# GR_Alim.net
KiCad netlist of a schematic drawn in Altium Designer
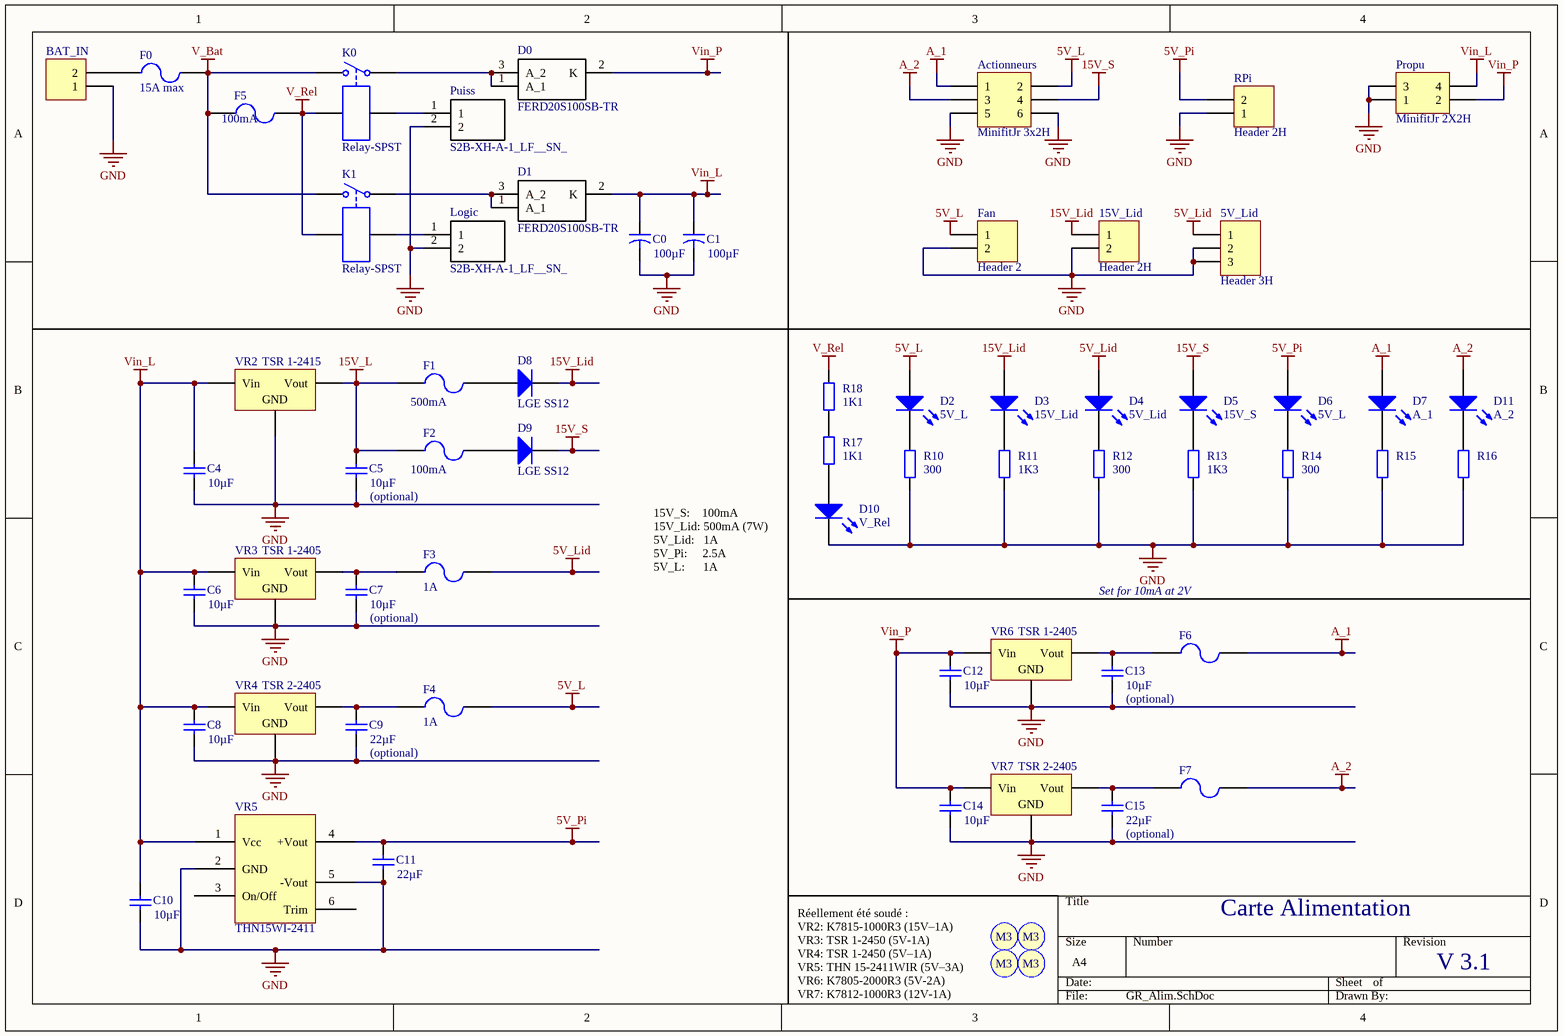
[diagram p0: GR_Alim.SchDoc]

(export (version "E")
  (design (tool "Eeschema 10.0.6"))
  (components
    (comp (ref "5V_Lid")
      (value "Header 3H")
      (footprint "S3B-XH-A")
      (description "Header, 3-Pin, Right Angle")
      (fields (field (name "PUBLISHER") "Altium Limited"))
      (libsource (lib "Miscellaneous Connectors") (part "Header 3H"))
    )
    (comp (ref "15V_Lid")
      (value "Header 2H")
      (footprint "S2B-XH-A")
      (description "Header, 2-Pin, Right Angle")
      (fields (field (name "PUBLISHER") "Altium Limited"))
      (libsource (lib "Miscellaneous Connectors") (part "Header 2H"))
    )
    (comp (ref "Actionneurs")
      (value "MinifitJr 3x2H")
      (footprint "MOLEX_MINIFITJR_3X2H")
      (description "Header, 3-Pin, Dual row, Right Angle")
      (fields (field (name "PUBLISHER") "Altium Limited"))
      (libsource (lib "Miscellaneous Connectors") (part "Header 3X2H"))
    )
    (comp (ref "BAT_IN")
      (value "Battery Onboard Solder")
      (footprint "Battery SALE")
      (description "Header, 2-Pin")
      (fields (field (name "PUBLISHER") "Altium Limited"))
      (libsource (lib "Miscellaneous Connectors") (part "Header 2"))
    )
    (comp (ref "C0")
      (value "100µF")
      (footprint "Condensateur")
      (description "Capacitor")
      (fields (field (name "Comment") "Cap2") (field (name "PUBLISHER") "Altium Limited"))
      (libsource (lib "Miscellaneous Devices") (part "Cap2"))
    )
    (comp (ref "C1")
      (value "100µF")
      (footprint "Condensateur")
      (description "Capacitor")
      (fields (field (name "Comment") "Cap2") (field (name "PUBLISHER") "Altium Limited"))
      (libsource (lib "Miscellaneous Devices") (part "Cap2"))
    )
    (comp (ref "C4")
      (value "10µF")
      (footprint "Capacitor 1206")
      (description "Capacitor")
      (fields (field (name "Comment") "Cap") (field (name "PUBLISHER") "Altium Limited"))
      (libsource (lib "Miscellaneous Devices") (part "Cap"))
    )
    (comp (ref "C5")
      (value "(optional)")
      (footprint "Capacitor 1206")
      (description "Capacitor")
      (fields (field (name "ALTIUM_VALUE") "10µF") (field (name "PUBLISHER") "Altium Limited"))
      (libsource (lib "Miscellaneous Devices") (part "Cap"))
    )
    (comp (ref "C6")
      (value "10µF")
      (footprint "Capacitor 1206")
      (description "Capacitor")
      (fields (field (name "Comment") "Cap") (field (name "PUBLISHER") "Altium Limited"))
      (libsource (lib "Miscellaneous Devices") (part "Cap"))
    )
    (comp (ref "C7")
      (value "(optional)")
      (footprint "Capacitor 1206")
      (description "Capacitor")
      (fields (field (name "ALTIUM_VALUE") "10µF") (field (name "PUBLISHER") "Altium Limited"))
      (libsource (lib "Miscellaneous Devices") (part "Cap"))
    )
    (comp (ref "C8")
      (value "10µF")
      (footprint "Capacitor 1206")
      (description "Capacitor")
      (fields (field (name "Comment") "Cap") (field (name "PUBLISHER") "Altium Limited"))
      (libsource (lib "Miscellaneous Devices") (part "Cap"))
    )
    (comp (ref "C9")
      (value "(optional)")
      (footprint "Capacitor 1206")
      (description "Capacitor")
      (fields (field (name "ALTIUM_VALUE") "22µF") (field (name "PUBLISHER") "Altium Limited"))
      (libsource (lib "Miscellaneous Devices") (part "Cap"))
    )
    (comp (ref "C10")
      (value "10µF")
      (footprint "Capacitor 1206")
      (description "Capacitor")
      (fields (field (name "Comment") "Cap") (field (name "PUBLISHER") "Altium Limited"))
      (libsource (lib "Miscellaneous Devices") (part "Cap"))
    )
    (comp (ref "C11")
      (value "22µF")
      (footprint "Capacitor 1206")
      (description "Capacitor")
      (fields (field (name "Comment") "Cap") (field (name "PUBLISHER") "Altium Limited"))
      (libsource (lib "Miscellaneous Devices") (part "Cap"))
    )
    (comp (ref "C12")
      (value "10µF")
      (footprint "Capacitor 1206")
      (description "Capacitor")
      (fields (field (name "Comment") "Cap") (field (name "PUBLISHER") "Altium Limited"))
      (libsource (lib "Miscellaneous Devices") (part "Cap"))
    )
    (comp (ref "C13")
      (value "(optional)")
      (footprint "Capacitor 1206")
      (description "Capacitor")
      (fields (field (name "ALTIUM_VALUE") "10µF") (field (name "PUBLISHER") "Altium Limited"))
      (libsource (lib "Miscellaneous Devices") (part "Cap"))
    )
    (comp (ref "C14")
      (value "10µF")
      (footprint "Capacitor 1206")
      (description "Capacitor")
      (fields (field (name "Comment") "Cap") (field (name "PUBLISHER") "Altium Limited"))
      (libsource (lib "Miscellaneous Devices") (part "Cap"))
    )
    (comp (ref "C15")
      (value "(optional)")
      (footprint "Capacitor 1206")
      (description "Capacitor")
      (fields (field (name "ALTIUM_VALUE") "22µF") (field (name "PUBLISHER") "Altium Limited"))
      (libsource (lib "Miscellaneous Devices") (part "Cap"))
    )
    (comp (ref "D0")
      (value "FERD20S100SB-TR")
      (footprint "SamacSys:FERD20H100SBTR")
      (description "Diode")
      (fields (field (name "MOUSER PART NUMBER") "511-FERD20S100SB-TR"))
      (libsource (lib "*") (part "FERD20S100SB-TR"))
    )
    (comp (ref "D1")
      (value "FERD20S100SB-TR")
      (footprint "SamacSys:FERD20H100SBTR")
      (description "Diode")
      (fields (field (name "MOUSER PART NUMBER") "511-FERD20S100SB-TR"))
      (libsource (lib "*") (part "FERD20S100SB-TR"))
    )
    (comp (ref "D2")
      (value "5V_L")
      (footprint "KP-3216SEC")
      (description "Typical RED, GREEN, YELLOW, AMBER GaAs LED")
      (fields (field (name "PUBLISHER") "Altium Limited"))
      (libsource (lib "Miscellaneous Devices") (part "LED2"))
    )
    (comp (ref "D3")
      (value "15V_Lid")
      (footprint "KP-3216SEC")
      (description "Typical RED, GREEN, YELLOW, AMBER GaAs LED")
      (fields (field (name "PUBLISHER") "Altium Limited"))
      (libsource (lib "Miscellaneous Devices") (part "LED2"))
    )
    (comp (ref "D4")
      (value "5V_Lid")
      (footprint "KP-3216SEC")
      (description "Typical RED, GREEN, YELLOW, AMBER GaAs LED")
      (fields (field (name "PUBLISHER") "Altium Limited"))
      (libsource (lib "Miscellaneous Devices") (part "LED2"))
    )
    (comp (ref "D5")
      (value "15V_S")
      (footprint "KP-3216SEC")
      (description "Typical RED, GREEN, YELLOW, AMBER GaAs LED")
      (fields (field (name "PUBLISHER") "Altium Limited"))
      (libsource (lib "Miscellaneous Devices") (part "LED2"))
    )
    (comp (ref "D6")
      (value "5V_L")
      (footprint "KP-3216SEC")
      (description "Typical RED, GREEN, YELLOW, AMBER GaAs LED")
      (fields (field (name "PUBLISHER") "Altium Limited"))
      (libsource (lib "Miscellaneous Devices") (part "LED2"))
    )
    (comp (ref "D7")
      (value "A_1")
      (footprint "KP-3216SEC")
      (description "Typical RED, GREEN, YELLOW, AMBER GaAs LED")
      (fields (field (name "PUBLISHER") "Altium Limited"))
      (libsource (lib "Miscellaneous Devices") (part "LED2"))
    )
    (comp (ref "D8")
      (value "LGE SS12")
      (footprint "SMB")
      (description "Default Diode")
      (fields (field (name "PUBLISHER") "Altium Limited"))
      (libsource (lib "Miscellaneous Devices") (part "Diode"))
    )
    (comp (ref "D9")
      (value "LGE SS12")
      (footprint "SMB")
      (description "Default Diode")
      (fields (field (name "PUBLISHER") "Altium Limited"))
      (libsource (lib "Miscellaneous Devices") (part "Diode"))
    )
    (comp (ref "D10")
      (value "V_Rel")
      (footprint "KP-3216SEC")
      (description "Typical RED, GREEN, YELLOW, AMBER GaAs LED")
      (fields (field (name "PUBLISHER") "Altium Limited"))
      (libsource (lib "Miscellaneous Devices") (part "LED2"))
    )
    (comp (ref "D11")
      (value "A_2")
      (footprint "KP-3216SEC")
      (description "Typical RED, GREEN, YELLOW, AMBER GaAs LED")
      (fields (field (name "PUBLISHER") "Altium Limited"))
      (libsource (lib "Miscellaneous Devices") (part "LED2"))
    )
    (comp (ref "F0")
      (value "15A max")
      (footprint "Fuse")
      (description "Main Fuse")
      (fields (field (name "PUBLISHER") "Altium Limited"))
      (libsource (lib "Miscellaneous Devices") (part "Fuse 2"))
    )
    (comp (ref "F1")
      (value "500mA")
      (footprint "3.5X2.8X1.9")
      (description "Resettable Fuse αA")
      (fields (field (name "PUBLISHER") "Altium Limited"))
      (libsource (lib "Miscellaneous Devices") (part "Fuse 2"))
    )
    (comp (ref "F2")
      (value "100mA")
      (footprint "3.5X2.8X1.9")
      (description "Resettable Fuse T0")
      (fields (field (name "PUBLISHER") "Altium Limited"))
      (libsource (lib "Miscellaneous Devices") (part "Fuse 2"))
    )
    (comp (ref "F3")
      (value "1A")
      (footprint "3.5X2.8X1.9")
      (description "Resettable Fuse JG")
      (fields (field (name "PUBLISHER") "Altium Limited"))
      (libsource (lib "Miscellaneous Devices") (part "Fuse 2"))
    )
    (comp (ref "F4")
      (value "1A")
      (footprint "3.5X2.8X1.9")
      (description "Resettable Fuse JG")
      (fields (field (name "PUBLISHER") "Altium Limited"))
      (libsource (lib "Miscellaneous Devices") (part "Fuse 2"))
    )
    (comp (ref "F5")
      (value "100mA")
      (footprint "3.5X2.8X1.9")
      (description "Fuse")
      (fields (field (name "PUBLISHER") "Altium Limited"))
      (libsource (lib "Miscellaneous Devices") (part "Fuse 2"))
    )
    (comp (ref "F6")
      (value "Fuse 2")
      (footprint "3.5X2.8X1.9")
      (description "Résistance 0Ω")
      (fields (field (name "PUBLISHER") "Altium Limited"))
      (libsource (lib "Miscellaneous Devices") (part "Fuse 2"))
    )
    (comp (ref "F7")
      (value "Fuse 2")
      (footprint "3.5X2.8X1.9")
      (description "Résistance 0Ω")
      (fields (field (name "PUBLISHER") "Altium Limited"))
      (libsource (lib "Miscellaneous Devices") (part "Fuse 2"))
    )
    (comp (ref "Fan")
      (value "Header 2")
      (footprint "HDR1X2")
      (description "Header, 2-Pin")
      (fields (field (name "PUBLISHER") "Altium Limited"))
      (libsource (lib "") (part "Header 2_1"))
    )
    (comp (ref "K0")
      (value "Relay-SPST")
      (footprint "Relay")
      (description "Single-Pole Single-Throw Relay")
      (fields (field (name "PUBLISHER") "Altium Limited"))
      (libsource (lib "Miscellaneous Devices") (part "Relay-SPST"))
    )
    (comp (ref "K1")
      (value "Relay-SPST")
      (footprint "Relay")
      (description "Single-Pole Single-Throw Relay")
      (fields (field (name "PUBLISHER") "Altium Limited"))
      (libsource (lib "Miscellaneous Devices") (part "Relay-SPST"))
    )
    (comp (ref "Logic")
      (value "S2B-XH-A-1_LF__SN_")
      (footprint "SamacSys:S2B-XH-A")
      (description "Connector")
      (fields (field (name "MANUFACTURER_PART_NUMBER") "S2B-XH-A-1(LF)(SN)"))
      (libsource (lib "SamacSys") (part "S2B-XH-A-1_LF__SN_"))
    )
    (comp (ref "Propu")
      (value "MinifitJr 2X2H")
      (footprint "MOLEX_MINIFITJR_2X2H")
      (description "Header, 2-Pin, Dual row, Right Angle")
      (fields (field (name "PUBLISHER") "Altium Limited"))
      (libsource (lib "Miscellaneous Connectors") (part "Header 2X2H"))
    )
    (comp (ref "Puiss")
      (value "S2B-XH-A-1_LF__SN_")
      (footprint "SamacSys:S2B-XH-A")
      (description "Connector")
      (fields (field (name "MANUFACTURER_PART_NUMBER") "S2B-XH-A-1(LF)(SN)"))
      (libsource (lib "SamacSys") (part "S2B-XH-A-1_LF__SN_"))
    )
    (comp (ref "R10")
      (value "300")
      (footprint "Resistor 1206")
      (description "Resistor")
      (fields (field (name "Comment") "Res2") (field (name "PUBLISHER") "Altium Limited"))
      (libsource (lib "Miscellaneous Devices") (part "Res2"))
    )
    (comp (ref "R11")
      (value "1K3")
      (footprint "Resistor 1206")
      (description "Resistor")
      (fields (field (name "Comment") "Res2") (field (name "PUBLISHER") "Altium Limited"))
      (libsource (lib "Miscellaneous Devices") (part "Res2"))
    )
    (comp (ref "R12")
      (value "300")
      (footprint "Resistor 1206")
      (description "Resistor")
      (fields (field (name "Comment") "Res2") (field (name "PUBLISHER") "Altium Limited"))
      (libsource (lib "Miscellaneous Devices") (part "Res2"))
    )
    (comp (ref "R13")
      (value "1K3")
      (footprint "Resistor 1206")
      (description "Resistor")
      (fields (field (name "Comment") "Res2") (field (name "PUBLISHER") "Altium Limited"))
      (libsource (lib "") (part "Res2_1"))
    )
    (comp (ref "R14")
      (value "300")
      (footprint "Resistor 1206")
      (description "Resistor")
      (fields (field (name "Comment") "Res2") (field (name "PUBLISHER") "Altium Limited"))
      (libsource (lib "") (part "Res2_1"))
    )
    (comp (ref "R15")
      (value "Res2")
      (footprint "Resistor 1206")
      (description "Resistor")
      (fields (field (name "PUBLISHER") "Altium Limited"))
      (libsource (lib "") (part "Res2_1"))
    )
    (comp (ref "R16")
      (value "Res2")
      (footprint "Resistor 1206")
      (description "Resistor")
      (fields (field (name "PUBLISHER") "Altium Limited"))
      (libsource (lib "") (part "Res2_1"))
    )
    (comp (ref "R17")
      (value "1K1")
      (footprint "Resistor 1206")
      (description "Resistor")
      (fields (field (name "Comment") "Res2") (field (name "PUBLISHER") "Altium Limited"))
      (libsource (lib "") (part "Res2_1"))
    )
    (comp (ref "R18")
      (value "1K1")
      (footprint "Resistor 1206")
      (description "Resistor")
      (fields (field (name "Comment") "Res2") (field (name "PUBLISHER") "Altium Limited"))
      (libsource (lib "") (part "Res2_1"))
    )
    (comp (ref "RPi")
      (value "Header 2H")
      (footprint "Molex_MiniFitJr_2x1H")
      (description "Header, 2-Pin, Right Angle")
      (fields (field (name "PUBLISHER") "Altium Limited"))
      (libsource (lib "") (part "Header 2H_1"))
    )
    (comp (ref "S1")
      (value "Screw M3")
      (footprint "Screw M3")
      (libsource (lib "Robot_2020") (part "Screw M3"))
    )
    (comp (ref "S2")
      (value "Screw M3")
      (footprint "Screw M3")
      (libsource (lib "Robot_2020") (part "Screw M3"))
    )
    (comp (ref "S3")
      (value "Screw M3")
      (footprint "Screw M3")
      (libsource (lib "Robot_2020") (part "Screw M3"))
    )
    (comp (ref "S4")
      (value "Screw M3")
      (footprint "Screw M3")
      (libsource (lib "Robot_2020") (part "Screw M3"))
    )
    (comp (ref "VR2")
      (value "TSR 1-2415")
      (footprint "TRS - Both")
      (description "Voltage Regulator")
      (fields (field (name "PUBLISHER") "Altium Limited"))
      (libsource (lib "Miscellaneous Devices") (part "Volt Reg"))
    )
    (comp (ref "VR3")
      (value "TSR 1-2405")
      (footprint "TRS - Both")
      (description "Voltage Regulator")
      (fields (field (name "PUBLISHER") "Altium Limited"))
      (libsource (lib "Miscellaneous Devices") (part "Volt Reg"))
    )
    (comp (ref "VR4")
      (value "TSR 2-2405")
      (footprint "TRS - Both")
      (description "Voltage Regulator")
      (fields (field (name "PUBLISHER") "Altium Limited"))
      (libsource (lib "Miscellaneous Devices") (part "Volt Reg"))
    )
    (comp (ref "VR5")
      (value "THN15WI-2411")
      (footprint "TRACO_1x1inch")
      (description "TRACO THN15WI-2411")
      (fields (field (name "PUBLISHER") "Altium Limited"))
      (libsource (lib "Robot_2020") (part "TEN60N"))
    )
    (comp (ref "VR6")
      (value "TSR 1-2405")
      (footprint "TRS - Both")
      (description "Voltage Regulator")
      (fields (field (name "PUBLISHER") "Altium Limited"))
      (libsource (lib "Miscellaneous Devices") (part "Volt Reg"))
    )
    (comp (ref "VR7")
      (value "TSR 2-2405")
      (footprint "TRS - Both")
      (description "Voltage Regulator")
      (fields (field (name "PUBLISHER") "Altium Limited"))
      (libsource (lib "Miscellaneous Devices") (part "Volt Reg"))
    )
  )
  (nets
    (net (code "1") (name "5V_L") (class "Default")
      (node (ref "Actionneurs") (pin "2") (pinfunction "2_2") (pintype "passive"))
      (node (ref "D2") (pin "1") (pinfunction "A_1") (pintype "passive"))
      (node (ref "F4") (pin "2") (pinfunction "2_2") (pintype "passive"))
      (node (ref "Fan") (pin "1") (pinfunction "1_1") (pintype "passive"))
    )
    (net (code "2") (name "5V_Lid") (class "Default")
      (node (ref "5V_Lid") (pin "1") (pinfunction "1_1") (pintype "passive"))
      (node (ref "D4") (pin "1") (pinfunction "A_1") (pintype "passive"))
      (node (ref "F3") (pin "2") (pinfunction "2_2") (pintype "passive"))
    )
    (net (code "3") (name "5V_Pi") (class "Default")
      (node (ref "C11") (pin "2") (pinfunction "2_2") (pintype "passive"))
      (node (ref "D6") (pin "1") (pinfunction "A_1") (pintype "passive"))
      (node (ref "RPi") (pin "2") (pinfunction "2_2") (pintype "passive"))
      (node (ref "VR5") (pin "4") (pinfunction "+Vout_4") (pintype "passive"))
    )
    (net (code "4") (name "15V_L") (class "Default")
      (node (ref "C5") (pin "2") (pinfunction "2_2") (pintype "passive"))
      (node (ref "F1") (pin "1") (pinfunction "1_1") (pintype "passive"))
      (node (ref "F2") (pin "1") (pinfunction "1_1") (pintype "passive"))
      (node (ref "VR2") (pin "3") (pinfunction "Vout_3") (pintype "passive"))
    )
    (net (code "5") (name "15V_Lid") (class "Default")
      (node (ref "15V_Lid") (pin "1") (pinfunction "1_1") (pintype "passive"))
      (node (ref "D3") (pin "1") (pinfunction "A_1") (pintype "passive"))
      (node (ref "D8") (pin "2") (pinfunction "K_2") (pintype "passive"))
    )
    (net (code "6") (name "15V_S") (class "Default")
      (node (ref "Actionneurs") (pin "4") (pinfunction "4_4") (pintype "passive"))
      (node (ref "D5") (pin "1") (pinfunction "A_1") (pintype "passive"))
      (node (ref "D9") (pin "2") (pinfunction "K_2") (pintype "passive"))
    )
    (net (code "7") (name "A_1") (class "Default")
      (node (ref "Actionneurs") (pin "1") (pinfunction "1_1") (pintype "passive"))
      (node (ref "D7") (pin "1") (pinfunction "A_1") (pintype "passive"))
      (node (ref "F6") (pin "2") (pinfunction "2_2") (pintype "passive"))
    )
    (net (code "8") (name "A_2") (class "Default")
      (node (ref "Actionneurs") (pin "3") (pinfunction "3_3") (pintype "passive"))
      (node (ref "D11") (pin "1") (pinfunction "A_1") (pintype "passive"))
      (node (ref "F7") (pin "2") (pinfunction "2_2") (pintype "passive"))
    )
    (net (code "9") (name "GND") (class "Default")
      (node (ref "15V_Lid") (pin "2") (pinfunction "2_2") (pintype "passive"))
      (node (ref "5V_Lid") (pin "2") (pinfunction "2_2") (pintype "passive"))
      (node (ref "5V_Lid") (pin "3") (pinfunction "3_3") (pintype "passive"))
      (node (ref "Actionneurs") (pin "5") (pinfunction "5_5") (pintype "passive"))
      (node (ref "Actionneurs") (pin "6") (pinfunction "6_6") (pintype "passive"))
      (node (ref "BAT_IN") (pin "1") (pinfunction "1_1") (pintype "passive"))
      (node (ref "C0") (pin "2") (pinfunction "2_2") (pintype "passive"))
      (node (ref "C1") (pin "2") (pinfunction "2_2") (pintype "passive"))
      (node (ref "C10") (pin "1") (pinfunction "1_1") (pintype "passive"))
      (node (ref "C11") (pin "1") (pinfunction "1_1") (pintype "passive"))
      (node (ref "C12") (pin "1") (pinfunction "1_1") (pintype "passive"))
      (node (ref "C13") (pin "1") (pinfunction "1_1") (pintype "passive"))
      (node (ref "C14") (pin "1") (pinfunction "1_1") (pintype "passive"))
      (node (ref "C15") (pin "1") (pinfunction "1_1") (pintype "passive"))
      (node (ref "C4") (pin "1") (pinfunction "1_1") (pintype "passive"))
      (node (ref "C5") (pin "1") (pinfunction "1_1") (pintype "passive"))
      (node (ref "C6") (pin "1") (pinfunction "1_1") (pintype "passive"))
      (node (ref "C7") (pin "1") (pinfunction "1_1") (pintype "passive"))
      (node (ref "C8") (pin "1") (pinfunction "1_1") (pintype "passive"))
      (node (ref "C9") (pin "1") (pinfunction "1_1") (pintype "passive"))
      (node (ref "D10") (pin "2") (pinfunction "K_2") (pintype "passive"))
      (node (ref "Fan") (pin "2") (pinfunction "2_2") (pintype "passive"))
      (node (ref "Logic") (pin "2") (pinfunction "2_2") (pintype "passive"))
      (node (ref "Propu") (pin "1") (pinfunction "1_1") (pintype "passive"))
      (node (ref "Propu") (pin "3") (pinfunction "3_3") (pintype "passive"))
      (node (ref "Puiss") (pin "2") (pinfunction "2_2") (pintype "passive"))
      (node (ref "R10") (pin "1") (pinfunction "1_1") (pintype "passive"))
      (node (ref "R11") (pin "1") (pinfunction "1_1") (pintype "passive"))
      (node (ref "R12") (pin "1") (pinfunction "1_1") (pintype "passive"))
      (node (ref "R13") (pin "2") (pinfunction "2_2") (pintype "passive"))
      (node (ref "R14") (pin "2") (pinfunction "2_2") (pintype "passive"))
      (node (ref "R15") (pin "2") (pinfunction "2_2") (pintype "passive"))
      (node (ref "R16") (pin "2") (pinfunction "2_2") (pintype "passive"))
      (node (ref "RPi") (pin "1") (pinfunction "1_1") (pintype "passive"))
      (node (ref "VR2") (pin "2") (pinfunction "GND_2") (pintype "passive"))
      (node (ref "VR3") (pin "2") (pinfunction "GND_2") (pintype "passive"))
      (node (ref "VR4") (pin "2") (pinfunction "GND_2") (pintype "passive"))
      (node (ref "VR5") (pin "2") (pinfunction "GND_2") (pintype "passive"))
      (node (ref "VR5") (pin "5") (pinfunction "-Vout_5") (pintype "passive"))
      (node (ref "VR6") (pin "2") (pinfunction "GND_2") (pintype "passive"))
      (node (ref "VR7") (pin "2") (pinfunction "GND_2") (pintype "passive"))
    )
    (net (code "10") (name "Net-(BAT_IN-Pad2)") (class "Default")
      (node (ref "BAT_IN") (pin "2") (pinfunction "2_2") (pintype "passive"))
      (node (ref "F0") (pin "1") (pinfunction "1_1") (pintype "passive"))
    )
    (net (code "11") (name "Net-(D0-A_1)") (class "Default")
      (node (ref "D0") (pin "1") (pinfunction "A_1_1") (pintype "passive"))
      (node (ref "D0") (pin "3") (pinfunction "A_2_3") (pintype "passive"))
      (node (ref "K0") (pin "1") (pinfunction "1_1") (pintype "passive"))
    )
    (net (code "12") (name "Net-(D1-A_1)") (class "Default")
      (node (ref "D1") (pin "1") (pinfunction "A_1_1") (pintype "passive"))
      (node (ref "D1") (pin "3") (pinfunction "A_2_3") (pintype "passive"))
      (node (ref "K1") (pin "1") (pinfunction "1_1") (pintype "passive"))
    )
    (net (code "13") (name "Net-(D2-K)") (class "Default")
      (node (ref "D2") (pin "2") (pinfunction "K_2") (pintype "passive"))
      (node (ref "R10") (pin "2") (pinfunction "2_2") (pintype "passive"))
    )
    (net (code "14") (name "Net-(D3-K)") (class "Default")
      (node (ref "D3") (pin "2") (pinfunction "K_2") (pintype "passive"))
      (node (ref "R11") (pin "2") (pinfunction "2_2") (pintype "passive"))
    )
    (net (code "15") (name "Net-(D4-K)") (class "Default")
      (node (ref "D4") (pin "2") (pinfunction "K_2") (pintype "passive"))
      (node (ref "R12") (pin "2") (pinfunction "2_2") (pintype "passive"))
    )
    (net (code "16") (name "Net-(D5-K)") (class "Default")
      (node (ref "D5") (pin "2") (pinfunction "K_2") (pintype "passive"))
      (node (ref "R13") (pin "1") (pinfunction "1_1") (pintype "passive"))
    )
    (net (code "17") (name "Net-(D6-K)") (class "Default")
      (node (ref "D6") (pin "2") (pinfunction "K_2") (pintype "passive"))
      (node (ref "R14") (pin "1") (pinfunction "1_1") (pintype "passive"))
    )
    (net (code "18") (name "Net-(D7-K)") (class "Default")
      (node (ref "D7") (pin "2") (pinfunction "K_2") (pintype "passive"))
      (node (ref "R15") (pin "1") (pinfunction "1_1") (pintype "passive"))
    )
    (net (code "19") (name "Net-(D8-A)") (class "Default")
      (node (ref "D8") (pin "1") (pinfunction "A_1") (pintype "passive"))
      (node (ref "F1") (pin "2") (pinfunction "2_2") (pintype "passive"))
    )
    (net (code "20") (name "Net-(D9-A)") (class "Default")
      (node (ref "D9") (pin "1") (pinfunction "A_1") (pintype "passive"))
      (node (ref "F2") (pin "2") (pinfunction "2_2") (pintype "passive"))
    )
    (net (code "21") (name "Net-(D10-A)") (class "Default")
      (node (ref "D10") (pin "1") (pinfunction "A_1") (pintype "passive"))
      (node (ref "R17") (pin "2") (pinfunction "2_2") (pintype "passive"))
    )
    (net (code "22") (name "Net-(D11-K)") (class "Default")
      (node (ref "D11") (pin "2") (pinfunction "K_2") (pintype "passive"))
      (node (ref "R16") (pin "1") (pinfunction "1_1") (pintype "passive"))
    )
    (net (code "23") (name "Net-(K0-Pad3)") (class "Default")
      (node (ref "K0") (pin "3") (pinfunction "3_3") (pintype "passive"))
      (node (ref "Puiss") (pin "1") (pinfunction "1_1") (pintype "passive"))
    )
    (net (code "24") (name "Net-(K1-Pad3)") (class "Default")
      (node (ref "K1") (pin "3") (pinfunction "3_3") (pintype "passive"))
      (node (ref "Logic") (pin "1") (pinfunction "1_1") (pintype "passive"))
    )
    (net (code "25") (name "Net-(R17-Pad1)") (class "Default")
      (node (ref "R17") (pin "1") (pinfunction "1_1") (pintype "passive"))
      (node (ref "R18") (pin "2") (pinfunction "2_2") (pintype "passive"))
    )
    (net (code "26") (name "Net-(VR3-Vout)") (class "Default")
      (node (ref "C7") (pin "2") (pinfunction "2_2") (pintype "passive"))
      (node (ref "F3") (pin "1") (pinfunction "1_1") (pintype "passive"))
      (node (ref "VR3") (pin "3") (pinfunction "Vout_3") (pintype "passive"))
    )
    (net (code "27") (name "Net-(VR4-Vout)") (class "Default")
      (node (ref "C9") (pin "2") (pinfunction "2_2") (pintype "passive"))
      (node (ref "F4") (pin "1") (pinfunction "1_1") (pintype "passive"))
      (node (ref "VR4") (pin "3") (pinfunction "Vout_3") (pintype "passive"))
    )
    (net (code "28") (name "Net-(VR6-Vout)") (class "Default")
      (node (ref "C13") (pin "2") (pinfunction "2_2") (pintype "passive"))
      (node (ref "F6") (pin "1") (pinfunction "1_1") (pintype "passive"))
      (node (ref "VR6") (pin "3") (pinfunction "Vout_3") (pintype "passive"))
    )
    (net (code "29") (name "Net-(VR7-Vout)") (class "Default")
      (node (ref "C15") (pin "2") (pinfunction "2_2") (pintype "passive"))
      (node (ref "F7") (pin "1") (pinfunction "1_1") (pintype "passive"))
      (node (ref "VR7") (pin "3") (pinfunction "Vout_3") (pintype "passive"))
    )
    (net (code "30") (name "V_Bat") (class "Default")
      (node (ref "F0") (pin "2") (pinfunction "2_2") (pintype "passive"))
      (node (ref "F5") (pin "1") (pinfunction "1_1") (pintype "passive"))
      (node (ref "K0") (pin "2") (pinfunction "2_2") (pintype "passive"))
      (node (ref "K1") (pin "2") (pinfunction "2_2") (pintype "passive"))
    )
    (net (code "31") (name "V_Rel") (class "Default")
      (node (ref "F5") (pin "2") (pinfunction "2_2") (pintype "passive"))
      (node (ref "K0") (pin "4") (pinfunction "4_4") (pintype "passive"))
      (node (ref "K1") (pin "4") (pinfunction "4_4") (pintype "passive"))
      (node (ref "R18") (pin "1") (pinfunction "1_1") (pintype "passive"))
    )
    (net (code "32") (name "Vin_L") (class "Default")
      (node (ref "C0") (pin "1") (pinfunction "1_1") (pintype "passive"))
      (node (ref "C1") (pin "1") (pinfunction "1_1") (pintype "passive"))
      (node (ref "C10") (pin "2") (pinfunction "2_2") (pintype "passive"))
      (node (ref "C4") (pin "2") (pinfunction "2_2") (pintype "passive"))
      (node (ref "C6") (pin "2") (pinfunction "2_2") (pintype "passive"))
      (node (ref "C8") (pin "2") (pinfunction "2_2") (pintype "passive"))
      (node (ref "D1") (pin "2") (pinfunction "K_2") (pintype "passive"))
      (node (ref "Propu") (pin "4") (pinfunction "4_4") (pintype "passive"))
      (node (ref "VR2") (pin "1") (pinfunction "Vin_1") (pintype "passive"))
      (node (ref "VR3") (pin "1") (pinfunction "Vin_1") (pintype "passive"))
      (node (ref "VR4") (pin "1") (pinfunction "Vin_1") (pintype "passive"))
      (node (ref "VR5") (pin "1") (pinfunction "Vcc_1") (pintype "passive"))
    )
    (net (code "33") (name "Vin_P") (class "Default")
      (node (ref "C12") (pin "2") (pinfunction "2_2") (pintype "passive"))
      (node (ref "C14") (pin "2") (pinfunction "2_2") (pintype "passive"))
      (node (ref "D0") (pin "2") (pinfunction "K_2") (pintype "passive"))
      (node (ref "Propu") (pin "2") (pinfunction "2_2") (pintype "passive"))
      (node (ref "VR6") (pin "1") (pinfunction "Vin_1") (pintype "passive"))
      (node (ref "VR7") (pin "1") (pinfunction "Vin_1") (pintype "passive"))
    )
    (net (code "34") (name "unconnected-(VR5-On{slash}Off-Pad3)") (class "Default")
      (node (ref "VR5") (pin "3") (pinfunction "On/Off_3") (pintype "passive"))
    )
    (net (code "35") (name "unconnected-(VR5-Trim-Pad6)") (class "Default")
      (node (ref "VR5") (pin "6") (pinfunction "Trim_6") (pintype "passive"))
    )
  )
)
